# 101_Connections.net
KiCad netlist of a schematic drawn in Altium Designer
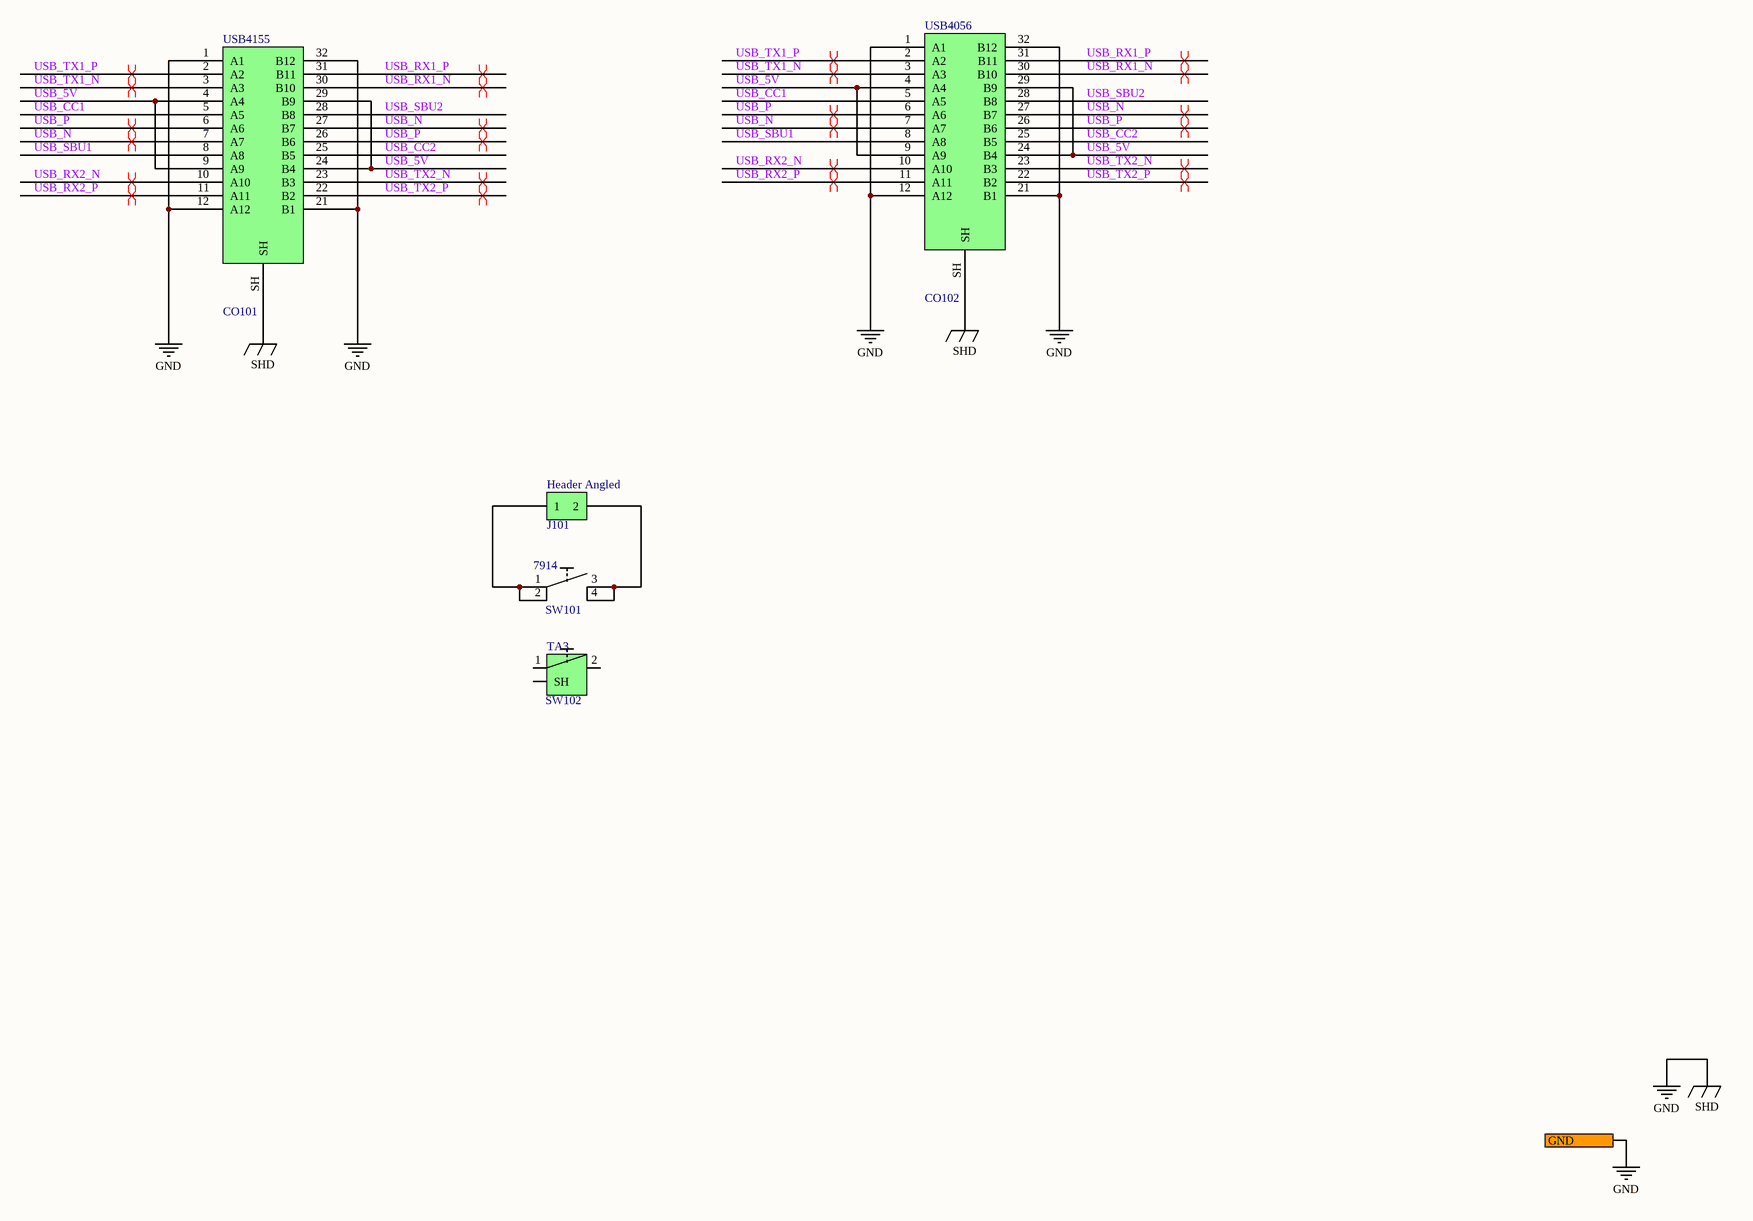
[diagram p0: 101_Connections.SchDoc]

(export (version "E")
  (design (tool "Eeschema 10.0.6"))
  (components
    (comp (ref "CO101")
      (value "USB4155")
      (footprint "USB4155-03-C")
      (description "USB C connector Plug Horizontal")
      (fields
        (field (name "REFVAL") "USB4155")
        (field (name "PART NUMBER") "CO0031")
        (field (name "MANFACTPART") "USB4155-03-C")
      )
      (libsource (lib "GTS_Database") (part "USB-CC"))
    )
    (comp (ref "CO102")
      (value "USB4056")
      (footprint "USB4056-03-A")
      (description "USB C connector Receptacle Horizontal")
      (fields
        (field (name "REFVAL") "USB4056")
        (field (name "PART NUMBER") "CO0030")
        (field (name "MANFACTPART") "USB4056-03-A")
      )
      (libsource (lib "GTS_Database") (part "USB-CC"))
    )
    (comp (ref "J101")
      (value "Header Angled")
      (footprint "1X2P_Angled_2.54mm")
      (description "Header Angled 1x2P")
      (fields
        (field (name "REFVAL") "Header Angled")
        (field (name "PART NUMBER") "CO0057")
        (field (name "MANFACTPART") "10129379-902001BLF")
      )
      (libsource (lib "GTS_Database") (part "CONN1X2P"))
    )
    (comp (ref "SW101")
      (value "7914")
      (footprint "7914S")
      (description "Tactile Switch Key Switch Right Angle")
      (fields
        (field (name "REFVAL") "7914")
        (field (name "PART NUMBER") "SW0004")
        (field (name "MANFACTPART") "7914S-1-050E")
      )
      (libsource (lib "GTS_Database") (part "SPST-2-4"))
    )
    (comp (ref "SW102")
      (value "TA3")
      (footprint "TA3")
      (description "Tactile Switch Right Angle")
      (fields
        (field (name "REFVAL") "TA3")
        (field (name "PART NUMBER") "SW0006")
        (field (name "MANFACTPART") "TA3-1W2-V-T/R")
      )
      (libsource (lib "GTS_Database") (part "SPST-2-SH"))
    )
  )
  (nets
    (net (code "1") (name "/USB_5V") (class "Default")
      (node (ref "CO101") (pin "24") (pinfunction "B4_24") (pintype "passive"))
      (node (ref "CO101") (pin "29") (pinfunction "B9_29") (pintype "passive"))
      (node (ref "CO101") (pin "4") (pinfunction "A4_4") (pintype "passive"))
      (node (ref "CO101") (pin "9") (pinfunction "A9_9") (pintype "passive"))
      (node (ref "CO102") (pin "24") (pinfunction "B4_24") (pintype "passive"))
      (node (ref "CO102") (pin "29") (pinfunction "B9_29") (pintype "passive"))
      (node (ref "CO102") (pin "4") (pinfunction "A4_4") (pintype "passive"))
      (node (ref "CO102") (pin "9") (pinfunction "A9_9") (pintype "passive"))
    )
    (net (code "2") (name "/USB_CC1") (class "Default")
      (node (ref "CO101") (pin "5") (pinfunction "A5_5") (pintype "passive"))
      (node (ref "CO102") (pin "5") (pinfunction "A5_5") (pintype "passive"))
    )
    (net (code "3") (name "/USB_CC2") (class "Default")
      (node (ref "CO101") (pin "25") (pinfunction "B5_25") (pintype "passive"))
      (node (ref "CO102") (pin "25") (pinfunction "B5_25") (pintype "passive"))
    )
    (net (code "4") (name "/USB_N") (class "Default")
      (node (ref "CO101") (pin "27") (pinfunction "B7_27") (pintype "passive"))
      (node (ref "CO101") (pin "7") (pinfunction "A7_7") (pintype "passive"))
      (node (ref "CO102") (pin "27") (pinfunction "B7_27") (pintype "passive"))
      (node (ref "CO102") (pin "7") (pinfunction "A7_7") (pintype "passive"))
    )
    (net (code "5") (name "/USB_P") (class "Default")
      (node (ref "CO101") (pin "26") (pinfunction "B6_26") (pintype "passive"))
      (node (ref "CO101") (pin "6") (pinfunction "A6_6") (pintype "passive"))
      (node (ref "CO102") (pin "26") (pinfunction "B6_26") (pintype "passive"))
      (node (ref "CO102") (pin "6") (pinfunction "A6_6") (pintype "passive"))
    )
    (net (code "6") (name "/USB_RX1_N") (class "Default")
      (node (ref "CO101") (pin "30") (pinfunction "B10_30") (pintype "passive"))
      (node (ref "CO102") (pin "30") (pinfunction "B10_30") (pintype "passive"))
    )
    (net (code "7") (name "/USB_RX1_P") (class "Default")
      (node (ref "CO101") (pin "31") (pinfunction "B11_31") (pintype "passive"))
      (node (ref "CO102") (pin "31") (pinfunction "B11_31") (pintype "passive"))
    )
    (net (code "8") (name "/USB_RX2_N") (class "Default")
      (node (ref "CO101") (pin "10") (pinfunction "A10_10") (pintype "passive"))
      (node (ref "CO102") (pin "10") (pinfunction "A10_10") (pintype "passive"))
    )
    (net (code "9") (name "/USB_RX2_P") (class "Default")
      (node (ref "CO101") (pin "11") (pinfunction "A11_11") (pintype "passive"))
      (node (ref "CO102") (pin "11") (pinfunction "A11_11") (pintype "passive"))
    )
    (net (code "10") (name "/USB_SBU1") (class "Default")
      (node (ref "CO101") (pin "8") (pinfunction "A8_8") (pintype "passive"))
      (node (ref "CO102") (pin "8") (pinfunction "A8_8") (pintype "passive"))
    )
    (net (code "11") (name "/USB_SBU2") (class "Default")
      (node (ref "CO101") (pin "28") (pinfunction "B8_28") (pintype "passive"))
      (node (ref "CO102") (pin "28") (pinfunction "B8_28") (pintype "passive"))
    )
    (net (code "12") (name "/USB_TX1_N") (class "Default")
      (node (ref "CO101") (pin "3") (pinfunction "A3_3") (pintype "passive"))
      (node (ref "CO102") (pin "3") (pinfunction "A3_3") (pintype "passive"))
    )
    (net (code "13") (name "/USB_TX1_P") (class "Default")
      (node (ref "CO101") (pin "2") (pinfunction "A2_2") (pintype "passive"))
      (node (ref "CO102") (pin "2") (pinfunction "A2_2") (pintype "passive"))
    )
    (net (code "14") (name "/USB_TX2_N") (class "Default")
      (node (ref "CO101") (pin "23") (pinfunction "B3_23") (pintype "passive"))
      (node (ref "CO102") (pin "23") (pinfunction "B3_23") (pintype "passive"))
    )
    (net (code "15") (name "/USB_TX2_P") (class "Default")
      (node (ref "CO101") (pin "22") (pinfunction "B2_22") (pintype "passive"))
      (node (ref "CO102") (pin "22") (pinfunction "B2_22") (pintype "passive"))
    )
    (net (code "16") (name "GND") (class "Default")
      (node (ref "CO101") (pin "1") (pinfunction "A1_1") (pintype "passive"))
      (node (ref "CO101") (pin "12") (pinfunction "A12_12") (pintype "passive"))
      (node (ref "CO101") (pin "21") (pinfunction "B1_21") (pintype "passive"))
      (node (ref "CO101") (pin "32") (pinfunction "B12_32") (pintype "passive"))
      (node (ref "CO101") (pin "SH") (pinfunction "SH_SH") (pintype "power_in"))
      (node (ref "CO102") (pin "1") (pinfunction "A1_1") (pintype "passive"))
      (node (ref "CO102") (pin "12") (pinfunction "A12_12") (pintype "passive"))
      (node (ref "CO102") (pin "21") (pinfunction "B1_21") (pintype "passive"))
      (node (ref "CO102") (pin "32") (pinfunction "B12_32") (pintype "passive"))
      (node (ref "CO102") (pin "SH") (pinfunction "SH_SH") (pintype "power_in"))
    )
    (net (code "17") (name "Net-(J101-Pad1)") (class "Default")
      (node (ref "J101") (pin "1") (pinfunction "1_1") (pintype "passive"))
      (node (ref "SW101") (pin "1") (pinfunction "1_1") (pintype "passive"))
      (node (ref "SW101") (pin "2") (pinfunction "2_2") (pintype "passive"))
    )
    (net (code "18") (name "Net-(J101-Pad2)") (class "Default")
      (node (ref "J101") (pin "2") (pinfunction "2_2") (pintype "passive"))
      (node (ref "SW101") (pin "3") (pinfunction "3_3") (pintype "passive"))
      (node (ref "SW101") (pin "4") (pinfunction "4_4") (pintype "passive"))
    )
    (net (code "19") (name "unconnected-(SW102-Pad1)") (class "Default")
      (node (ref "SW102") (pin "1") (pinfunction "1_1") (pintype "passive"))
    )
    (net (code "20") (name "unconnected-(SW102-Pad2)") (class "Default")
      (node (ref "SW102") (pin "2") (pinfunction "2_2") (pintype "passive"))
    )
    (net (code "21") (name "unconnected-(SW102-SH-Pad3)") (class "Default")
      (node (ref "SW102") (pin "3") (pinfunction "SH_3") (pintype "passive"))
    )
  )
)
